# leakage.net
KiCad netlist of a schematic drawn in EAGLE
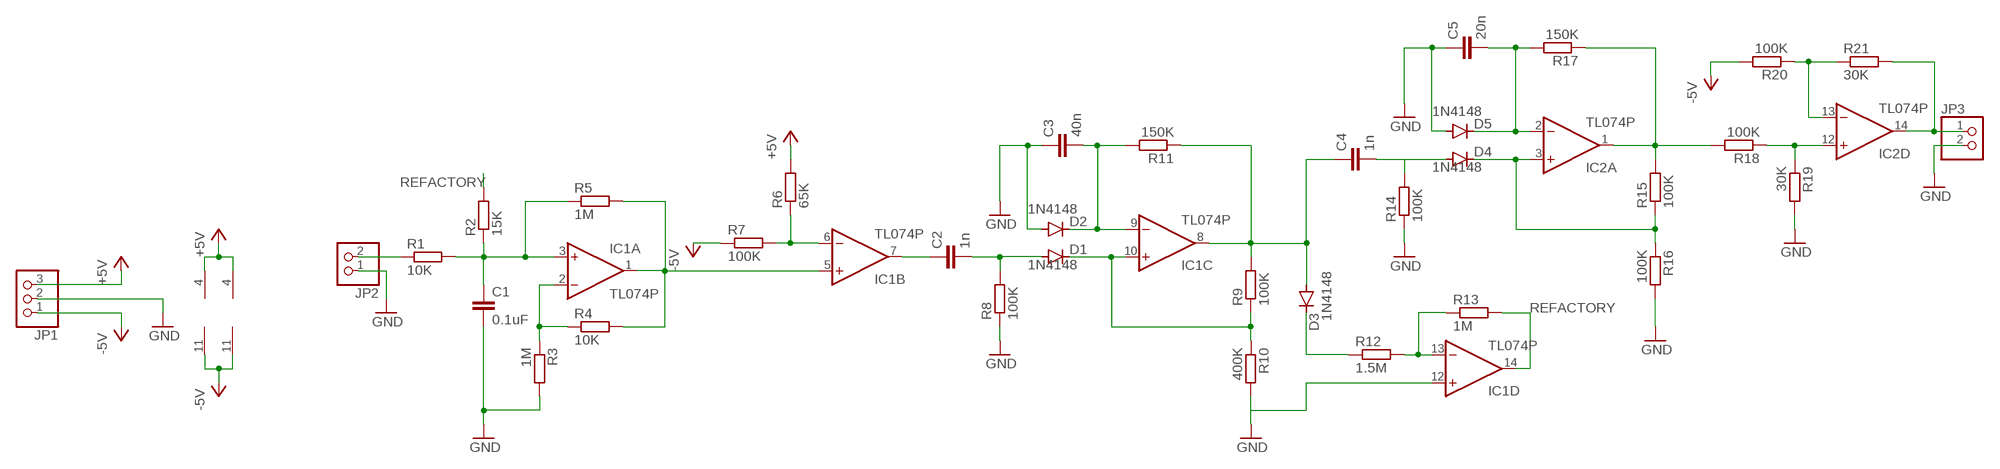
[diagram p0: schematic, sheet 1]

(export (version "E")
  (design (tool "Eeschema 10.0.6"))
  (components
    (comp (ref "C1")
      (value "0.1uF")
      (footprint "eagle-import:C025-025X050")
      (libsource (lib "eagle-import") (part "C-EU025-025X050"))
    )
    (comp (ref "C2")
      (value "1n")
      (footprint "eagle-import:C025-025X050")
      (libsource (lib "eagle-import") (part "C-EU025-025X050"))
    )
    (comp (ref "C3")
      (value "40n")
      (footprint "eagle-import:C025-025X050")
      (libsource (lib "eagle-import") (part "C-EU025-025X050"))
    )
    (comp (ref "C4")
      (value "1n")
      (footprint "eagle-import:C025-025X050")
      (libsource (lib "eagle-import") (part "C-EU025-025X050"))
    )
    (comp (ref "C5")
      (value "20n")
      (footprint "eagle-import:C025-025X050")
      (libsource (lib "eagle-import") (part "C-EU025-025X050"))
    )
    (comp (ref "D1")
      (value "1N4148")
      (footprint "eagle-import:DO35-10")
      (libsource (lib "eagle-import") (part "1N4148DO35-10"))
    )
    (comp (ref "D2")
      (value "1N4148")
      (footprint "eagle-import:DO35-10")
      (libsource (lib "eagle-import") (part "1N4148DO35-10"))
    )
    (comp (ref "D3")
      (value "1N4148")
      (footprint "eagle-import:DO35-10")
      (libsource (lib "eagle-import") (part "1N4148DO35-10"))
    )
    (comp (ref "D4")
      (value "1N4148")
      (footprint "eagle-import:DO35-10")
      (libsource (lib "eagle-import") (part "1N4148DO35-10"))
    )
    (comp (ref "D5")
      (value "1N4148")
      (footprint "eagle-import:DO35-10")
      (libsource (lib "eagle-import") (part "1N4148DO35-10"))
    )
    (comp (ref "IC1")
      (value "TL074P")
      (footprint "eagle-import:DIL14")
      (libsource (lib "eagle-import") (part "TL074P"))
    )
    (comp (ref "IC2")
      (value "TL074P")
      (footprint "eagle-import:DIL14")
      (libsource (lib "eagle-import") (part "TL074P"))
    )
    (comp (ref "JP1")
      (value "PINHD-1X3")
      (footprint "eagle-import:1X03")
      (libsource (lib "eagle-import") (part "PINHD-1X3"))
    )
    (comp (ref "JP2")
      (value "PINHD-1X2")
      (footprint "eagle-import:1X02")
      (libsource (lib "eagle-import") (part "PINHD-1X2"))
    )
    (comp (ref "JP3")
      (value "PINHD-1X2")
      (footprint "eagle-import:1X02")
      (libsource (lib "eagle-import") (part "PINHD-1X2"))
    )
    (comp (ref "R1")
      (value "10K")
      (footprint "eagle-import:0207_10")
      (libsource (lib "eagle-import") (part "R-EU_0207/10"))
    )
    (comp (ref "R2")
      (value "15K")
      (footprint "eagle-import:0207_10")
      (libsource (lib "eagle-import") (part "R-EU_0207/10"))
    )
    (comp (ref "R3")
      (value "1M")
      (footprint "eagle-import:0207_10")
      (libsource (lib "eagle-import") (part "R-EU_0207/10"))
    )
    (comp (ref "R4")
      (value "10K")
      (footprint "eagle-import:0207_10")
      (libsource (lib "eagle-import") (part "R-EU_0207/10"))
    )
    (comp (ref "R5")
      (value "1M")
      (footprint "eagle-import:0207_10")
      (libsource (lib "eagle-import") (part "R-EU_0207/10"))
    )
    (comp (ref "R6")
      (value "65K")
      (footprint "eagle-import:0207_10")
      (libsource (lib "eagle-import") (part "R-EU_0207/10"))
    )
    (comp (ref "R7")
      (value "100K")
      (footprint "eagle-import:0207_10")
      (libsource (lib "eagle-import") (part "R-EU_0207/10"))
    )
    (comp (ref "R8")
      (value "100K")
      (footprint "eagle-import:0207_10")
      (libsource (lib "eagle-import") (part "R-EU_0207/10"))
    )
    (comp (ref "R9")
      (value "100K")
      (footprint "eagle-import:0207_10")
      (libsource (lib "eagle-import") (part "R-EU_0207/10"))
    )
    (comp (ref "R10")
      (value "400K")
      (footprint "eagle-import:0207_10")
      (libsource (lib "eagle-import") (part "R-EU_0207/10"))
    )
    (comp (ref "R11")
      (value "150K")
      (footprint "eagle-import:0207_10")
      (libsource (lib "eagle-import") (part "R-EU_0207/10"))
    )
    (comp (ref "R12")
      (value "1.5M")
      (footprint "eagle-import:0207_10")
      (libsource (lib "eagle-import") (part "R-EU_0207/10"))
    )
    (comp (ref "R13")
      (value "1M")
      (footprint "eagle-import:0207_10")
      (libsource (lib "eagle-import") (part "R-EU_0207/10"))
    )
    (comp (ref "R14")
      (value "100K")
      (footprint "eagle-import:0207_10")
      (libsource (lib "eagle-import") (part "R-EU_0207/10"))
    )
    (comp (ref "R15")
      (value "100K")
      (footprint "eagle-import:0207_10")
      (libsource (lib "eagle-import") (part "R-EU_0207/10"))
    )
    (comp (ref "R16")
      (value "100K")
      (footprint "eagle-import:0207_10")
      (libsource (lib "eagle-import") (part "R-EU_0207/10"))
    )
    (comp (ref "R17")
      (value "150K")
      (footprint "eagle-import:0207_10")
      (libsource (lib "eagle-import") (part "R-EU_0207/10"))
    )
    (comp (ref "R18")
      (value "100K")
      (footprint "eagle-import:0207_10")
      (libsource (lib "eagle-import") (part "R-EU_0207/10"))
    )
    (comp (ref "R19")
      (value "30K")
      (footprint "eagle-import:0207_10")
      (libsource (lib "eagle-import") (part "R-EU_0207/10"))
    )
    (comp (ref "R20")
      (value "100K")
      (footprint "eagle-import:0207_10")
      (libsource (lib "eagle-import") (part "R-EU_0207/10"))
    )
    (comp (ref "R21")
      (value "30K")
      (footprint "eagle-import:0207_10")
      (libsource (lib "eagle-import") (part "R-EU_0207/10"))
    )
  )
  (nets
    (net (code "1") (name "+5V") (class "Default")
      (node (ref "IC1") (pin "4") (pinfunction "V+_4") (pintype "power_in"))
      (node (ref "IC2") (pin "4") (pinfunction "V+_4") (pintype "power_in"))
      (node (ref "JP1") (pin "3") (pinfunction "3_3") (pintype "passive"))
      (node (ref "R6") (pin "2") (pinfunction "2_2") (pintype "passive"))
    )
    (net (code "2") (name "-5V") (class "Default")
      (node (ref "IC1") (pin "11") (pinfunction "V-_11") (pintype "power_in"))
      (node (ref "IC2") (pin "11") (pinfunction "V-_11") (pintype "power_in"))
      (node (ref "JP1") (pin "1") (pinfunction "1_1") (pintype "passive"))
      (node (ref "R20") (pin "2") (pinfunction "2_2") (pintype "passive"))
      (node (ref "R7") (pin "1") (pinfunction "1_1") (pintype "passive"))
    )
    (net (code "3") (name "/REFACTORY") (class "Default")
      (node (ref "IC1") (pin "14") (pinfunction "OUT_14") (pintype "output"))
      (node (ref "R13") (pin "2") (pinfunction "2_2") (pintype "passive"))
      (node (ref "R2") (pin "2") (pinfunction "2_2") (pintype "passive"))
    )
    (net (code "4") (name "GND") (class "Default")
      (node (ref "C1") (pin "2") (pinfunction "2_2") (pintype "passive"))
      (node (ref "C3") (pin "1") (pinfunction "1_1") (pintype "passive"))
      (node (ref "C5") (pin "1") (pinfunction "1_1") (pintype "passive"))
      (node (ref "D2") (pin "A") (pinfunction "A_A") (pintype "passive"))
      (node (ref "D5") (pin "A") (pinfunction "A_A") (pintype "passive"))
      (node (ref "IC1") (pin "12") (pinfunction "+IN_12") (pintype "input"))
      (node (ref "JP1") (pin "2") (pinfunction "2_2") (pintype "passive"))
      (node (ref "JP2") (pin "1") (pinfunction "1_1") (pintype "passive"))
      (node (ref "JP3") (pin "2") (pinfunction "2_2") (pintype "passive"))
      (node (ref "R10") (pin "2") (pinfunction "2_2") (pintype "passive"))
      (node (ref "R14") (pin "1") (pinfunction "1_1") (pintype "passive"))
      (node (ref "R16") (pin "2") (pinfunction "2_2") (pintype "passive"))
      (node (ref "R19") (pin "2") (pinfunction "2_2") (pintype "passive"))
      (node (ref "R3") (pin "2") (pinfunction "2_2") (pintype "passive"))
      (node (ref "R8") (pin "1") (pinfunction "1_1") (pintype "passive"))
    )
    (net (code "5") (name "Net-(C2-Pad2)") (class "Default")
      (node (ref "C2") (pin "2") (pinfunction "2_2") (pintype "passive"))
      (node (ref "D1") (pin "A") (pinfunction "A_A") (pintype "passive"))
      (node (ref "R8") (pin "2") (pinfunction "2_2") (pintype "passive"))
    )
    (net (code "6") (name "Net-(C4-Pad2)") (class "Default")
      (node (ref "C4") (pin "2") (pinfunction "2_2") (pintype "passive"))
      (node (ref "D4") (pin "A") (pinfunction "A_A") (pintype "passive"))
      (node (ref "R14") (pin "2") (pinfunction "2_2") (pintype "passive"))
    )
    (net (code "7") (name "Net-(D3-PadC)") (class "Default")
      (node (ref "D3") (pin "C") (pinfunction "C_C") (pintype "passive"))
      (node (ref "R12") (pin "1") (pinfunction "1_1") (pintype "passive"))
    )
    (net (code "8") (name "Net-(IC1A-+IN)") (class "Default")
      (node (ref "C1") (pin "1") (pinfunction "1_1") (pintype "passive"))
      (node (ref "IC1") (pin "3") (pinfunction "+IN_3") (pintype "input"))
      (node (ref "R1") (pin "2") (pinfunction "2_2") (pintype "passive"))
      (node (ref "R2") (pin "1") (pinfunction "1_1") (pintype "passive"))
      (node (ref "R5") (pin "1") (pinfunction "1_1") (pintype "passive"))
    )
    (net (code "9") (name "Net-(IC1A--IN)") (class "Default")
      (node (ref "IC1") (pin "2") (pinfunction "-IN_2") (pintype "input"))
      (node (ref "R3") (pin "1") (pinfunction "1_1") (pintype "passive"))
      (node (ref "R4") (pin "1") (pinfunction "1_1") (pintype "passive"))
    )
    (net (code "10") (name "Net-(IC1A-OUT)") (class "Default")
      (node (ref "IC1") (pin "1") (pinfunction "OUT_1") (pintype "output"))
      (node (ref "IC1") (pin "5") (pinfunction "+IN_5") (pintype "input"))
      (node (ref "R4") (pin "2") (pinfunction "2_2") (pintype "passive"))
      (node (ref "R5") (pin "2") (pinfunction "2_2") (pintype "passive"))
    )
    (net (code "11") (name "Net-(IC1B--IN)") (class "Default")
      (node (ref "IC1") (pin "6") (pinfunction "-IN_6") (pintype "input"))
      (node (ref "R6") (pin "1") (pinfunction "1_1") (pintype "passive"))
      (node (ref "R7") (pin "2") (pinfunction "2_2") (pintype "passive"))
    )
    (net (code "12") (name "Net-(IC1B-OUT)") (class "Default")
      (node (ref "C2") (pin "1") (pinfunction "1_1") (pintype "passive"))
      (node (ref "IC1") (pin "7") (pinfunction "OUT_7") (pintype "output"))
    )
    (net (code "13") (name "Net-(IC1C-+IN)") (class "Default")
      (node (ref "D1") (pin "C") (pinfunction "C_C") (pintype "passive"))
      (node (ref "IC1") (pin "10") (pinfunction "+IN_10") (pintype "input"))
      (node (ref "R10") (pin "1") (pinfunction "1_1") (pintype "passive"))
      (node (ref "R9") (pin "1") (pinfunction "1_1") (pintype "passive"))
    )
    (net (code "14") (name "Net-(IC1C--IN)") (class "Default")
      (node (ref "C3") (pin "2") (pinfunction "2_2") (pintype "passive"))
      (node (ref "D2") (pin "C") (pinfunction "C_C") (pintype "passive"))
      (node (ref "IC1") (pin "9") (pinfunction "-IN_9") (pintype "input"))
      (node (ref "R11") (pin "2") (pinfunction "2_2") (pintype "passive"))
    )
    (net (code "15") (name "Net-(IC1C-OUT)") (class "Default")
      (node (ref "C4") (pin "1") (pinfunction "1_1") (pintype "passive"))
      (node (ref "D3") (pin "A") (pinfunction "A_A") (pintype "passive"))
      (node (ref "IC1") (pin "8") (pinfunction "OUT_8") (pintype "output"))
      (node (ref "R11") (pin "1") (pinfunction "1_1") (pintype "passive"))
      (node (ref "R9") (pin "2") (pinfunction "2_2") (pintype "passive"))
    )
    (net (code "16") (name "Net-(IC1D--IN)") (class "Default")
      (node (ref "IC1") (pin "13") (pinfunction "-IN_13") (pintype "input"))
      (node (ref "R12") (pin "2") (pinfunction "2_2") (pintype "passive"))
      (node (ref "R13") (pin "1") (pinfunction "1_1") (pintype "passive"))
    )
    (net (code "17") (name "Net-(IC2A-+IN)") (class "Default")
      (node (ref "D4") (pin "C") (pinfunction "C_C") (pintype "passive"))
      (node (ref "IC2") (pin "3") (pinfunction "+IN_3") (pintype "input"))
      (node (ref "R15") (pin "1") (pinfunction "1_1") (pintype "passive"))
      (node (ref "R16") (pin "1") (pinfunction "1_1") (pintype "passive"))
    )
    (net (code "18") (name "Net-(IC2A--IN)") (class "Default")
      (node (ref "C5") (pin "2") (pinfunction "2_2") (pintype "passive"))
      (node (ref "D5") (pin "C") (pinfunction "C_C") (pintype "passive"))
      (node (ref "IC2") (pin "2") (pinfunction "-IN_2") (pintype "input"))
      (node (ref "R17") (pin "2") (pinfunction "2_2") (pintype "passive"))
    )
    (net (code "19") (name "Net-(IC2A-OUT)") (class "Default")
      (node (ref "IC2") (pin "1") (pinfunction "OUT_1") (pintype "output"))
      (node (ref "R15") (pin "2") (pinfunction "2_2") (pintype "passive"))
      (node (ref "R17") (pin "1") (pinfunction "1_1") (pintype "passive"))
      (node (ref "R18") (pin "2") (pinfunction "2_2") (pintype "passive"))
    )
    (net (code "20") (name "Net-(IC2D-+IN)") (class "Default")
      (node (ref "IC2") (pin "12") (pinfunction "+IN_12") (pintype "input"))
      (node (ref "R18") (pin "1") (pinfunction "1_1") (pintype "passive"))
      (node (ref "R19") (pin "1") (pinfunction "1_1") (pintype "passive"))
    )
    (net (code "21") (name "Net-(IC2D--IN)") (class "Default")
      (node (ref "IC2") (pin "13") (pinfunction "-IN_13") (pintype "input"))
      (node (ref "R20") (pin "1") (pinfunction "1_1") (pintype "passive"))
      (node (ref "R21") (pin "1") (pinfunction "1_1") (pintype "passive"))
    )
    (net (code "22") (name "Net-(IC2D-OUT)") (class "Default")
      (node (ref "IC2") (pin "14") (pinfunction "OUT_14") (pintype "output"))
      (node (ref "JP3") (pin "1") (pinfunction "1_1") (pintype "passive"))
      (node (ref "R21") (pin "2") (pinfunction "2_2") (pintype "passive"))
    )
    (net (code "23") (name "Net-(JP2-Pad2)") (class "Default")
      (node (ref "JP2") (pin "2") (pinfunction "2_2") (pintype "passive"))
      (node (ref "R1") (pin "1") (pinfunction "1_1") (pintype "passive"))
    )
  )
)
